# Fonte.net
KiCad netlist of a schematic drawn in Altium Designer
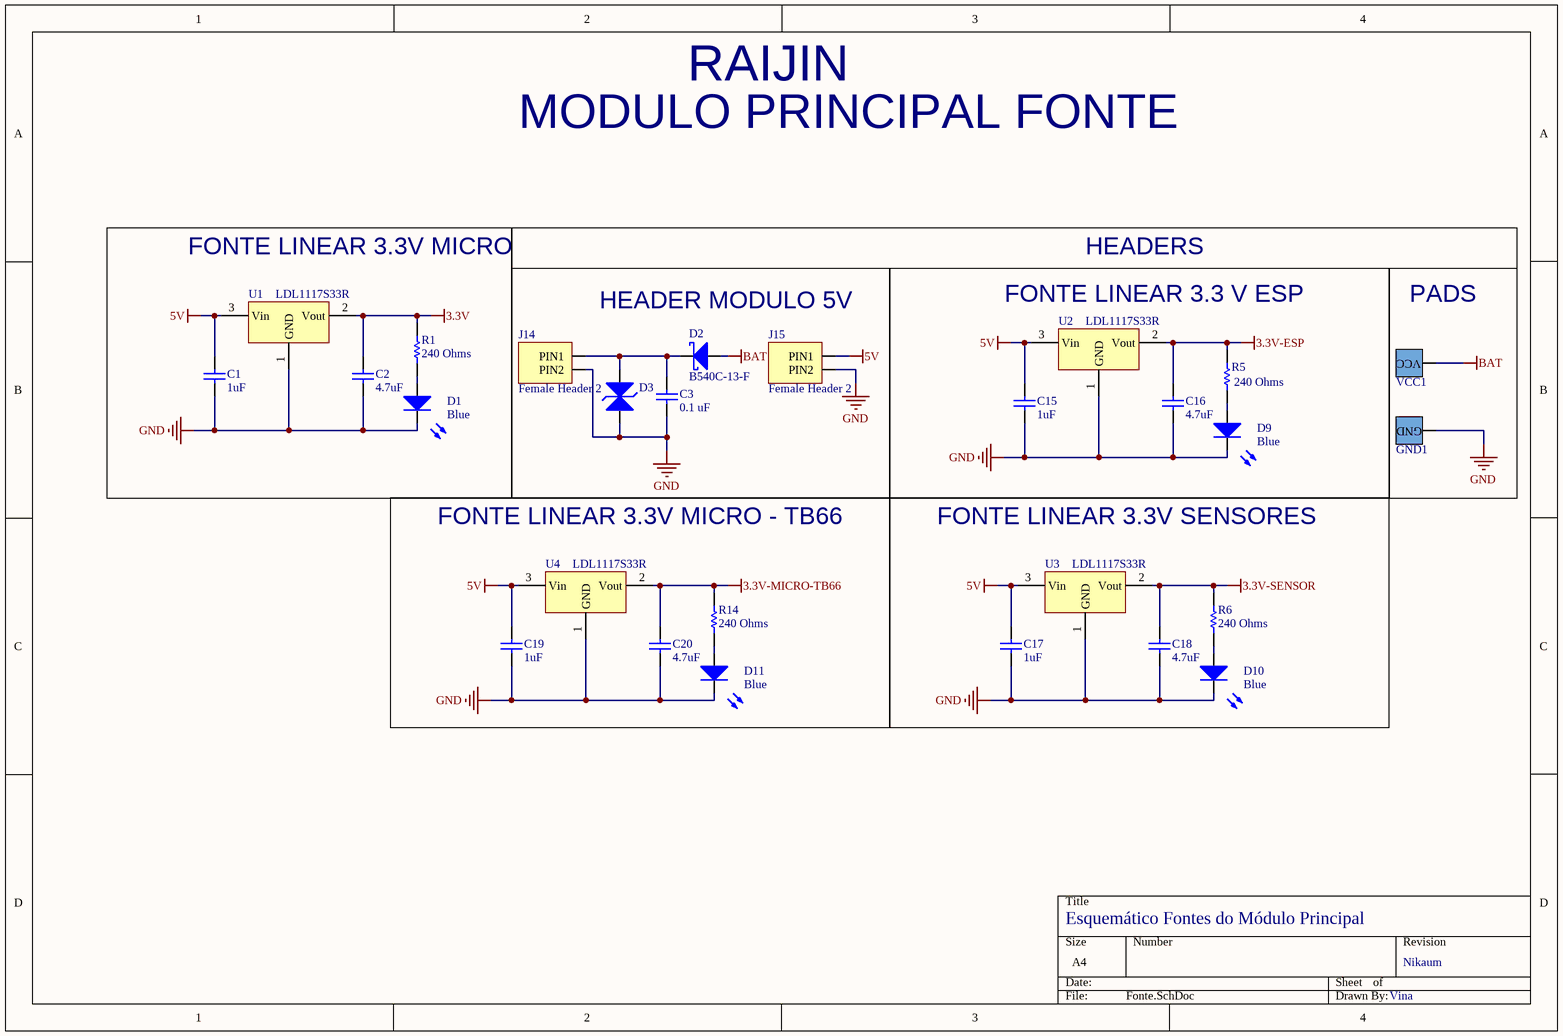
[diagram p0: Fonte.SchDoc]

(export (version "E")
  (design (tool "Eeschema 10.0.6"))
  (components
    (comp (ref "C1")
      (value "1uF")
      (footprint "C0805")
      (description "CAP CER 1uF 25V X5R 0805")
      (fields
        (field (name "MANUFACTURER") "Wurth Electronik")
        (field (name "PART NUMBER") "885012107015")
        (field (name "LIBRARY CONTROL - PERSON THAT CHECKED FOOTPRINT") "Nikaum")
        (field (name "LIBRARY CONTROL - PERSON THAT CHECKED SCHEMATIC") "Nikaum")
        (field (name "LIBRARY CONTROL - PERSON THAT DID THE LAST UPDATE FOOTPRINT") "Nikaum")
        (field (name "LIBRARY CONTROL - PERSON THAT DID THE LAST UPDATE SCHEMATIC") "Nikaum")
      )
      (libsource (lib "Uai!Tecas") (part "885012107015"))
    )
    (comp (ref "C2")
      (value "4.7uF")
      (footprint "C0805")
      (description "CAP CER 4.7uF 25V 20% 0805")
      (fields
        (field (name "MANUFACTURER") "Walsin")
        (field (name "PART NUMBER") "0805X475M250CT")
        (field (name "LIBRARY CONTROL - PERSON THAT CHECKED SCHEMATIC") "Guilherme")
        (field (name "LIBRARY CONTROL - PERSON THAT DID THE LAST UPDATE SCHEMATIC") "Marcos")
      )
      (libsource (lib "Uai!Tecas") (part "0805X475M250CT"))
    )
    (comp (ref "C3")
      (value "0.1 uF")
      (footprint "C0805")
      (description "CAP CER 0.1uF 50V X7R 0805")
      (fields
        (field (name "MANUFACTURER") "Kemet")
        (field (name "PART NUMBER") "C0805C104K5RACTU")
        (field (name "LIBRARY CONTROL - PERSON THAT CHECKED SCHEMATIC") "Guilherme")
        (field (name "LIBRARY CONTROL - PERSON THAT DID THE LAST UPDATE SCHEMATIC") "Marcos")
      )
      (libsource (lib "Uai!Tecas") (part "C0805C104K5RACTU"))
    )
    (comp (ref "C15")
      (value "1uF")
      (footprint "C0805")
      (description "CAP CER 1uF 25V X5R 0805")
      (fields
        (field (name "MANUFACTURER") "Wurth Electronik")
        (field (name "PART NUMBER") "885012107015")
        (field (name "LIBRARY CONTROL - PERSON THAT CHECKED FOOTPRINT") "Nikaum")
        (field (name "LIBRARY CONTROL - PERSON THAT CHECKED SCHEMATIC") "Nikaum")
        (field (name "LIBRARY CONTROL - PERSON THAT DID THE LAST UPDATE FOOTPRINT") "Nikaum")
        (field (name "LIBRARY CONTROL - PERSON THAT DID THE LAST UPDATE SCHEMATIC") "Nikaum")
      )
      (libsource (lib "Uai!Tecas") (part "885012107015"))
    )
    (comp (ref "C16")
      (value "4.7uF")
      (footprint "C0805")
      (description "CAP CER 4.7uF 25V 20% 0805")
      (fields
        (field (name "MANUFACTURER") "Walsin")
        (field (name "PART NUMBER") "0805X475M250CT")
        (field (name "LIBRARY CONTROL - PERSON THAT CHECKED SCHEMATIC") "Guilherme")
        (field (name "LIBRARY CONTROL - PERSON THAT DID THE LAST UPDATE SCHEMATIC") "Marcos")
      )
      (libsource (lib "Uai!Tecas") (part "0805X475M250CT"))
    )
    (comp (ref "C17")
      (value "1uF")
      (footprint "C0805")
      (description "CAP CER 1uF 25V X5R 0805")
      (fields
        (field (name "MANUFACTURER") "Wurth Electronik")
        (field (name "PART NUMBER") "885012107015")
        (field (name "LIBRARY CONTROL - PERSON THAT CHECKED FOOTPRINT") "Nikaum")
        (field (name "LIBRARY CONTROL - PERSON THAT CHECKED SCHEMATIC") "Nikaum")
        (field (name "LIBRARY CONTROL - PERSON THAT DID THE LAST UPDATE FOOTPRINT") "Nikaum")
        (field (name "LIBRARY CONTROL - PERSON THAT DID THE LAST UPDATE SCHEMATIC") "Nikaum")
      )
      (libsource (lib "Uai!Tecas") (part "885012107015"))
    )
    (comp (ref "C18")
      (value "4.7uF")
      (footprint "C0805")
      (description "CAP CER 4.7uF 25V 20% 0805")
      (fields
        (field (name "MANUFACTURER") "Walsin")
        (field (name "PART NUMBER") "0805X475M250CT")
        (field (name "LIBRARY CONTROL - PERSON THAT CHECKED SCHEMATIC") "Guilherme")
        (field (name "LIBRARY CONTROL - PERSON THAT DID THE LAST UPDATE SCHEMATIC") "Marcos")
      )
      (libsource (lib "Uai!Tecas") (part "0805X475M250CT"))
    )
    (comp (ref "C19")
      (value "1uF")
      (footprint "C0805")
      (description "CAP CER 1uF 25V X5R 0805")
      (fields
        (field (name "MANUFACTURER") "Wurth Electronik")
        (field (name "PART NUMBER") "885012107015")
        (field (name "LIBRARY CONTROL - PERSON THAT CHECKED FOOTPRINT") "Nikaum")
        (field (name "LIBRARY CONTROL - PERSON THAT CHECKED SCHEMATIC") "Nikaum")
        (field (name "LIBRARY CONTROL - PERSON THAT DID THE LAST UPDATE FOOTPRINT") "Nikaum")
        (field (name "LIBRARY CONTROL - PERSON THAT DID THE LAST UPDATE SCHEMATIC") "Nikaum")
      )
      (libsource (lib "Uai!Tecas") (part "885012107015"))
    )
    (comp (ref "C20")
      (value "4.7uF")
      (footprint "C0805")
      (description "CAP CER 4.7uF 25V 20% 0805")
      (fields
        (field (name "MANUFACTURER") "Walsin")
        (field (name "PART NUMBER") "0805X475M250CT")
        (field (name "LIBRARY CONTROL - PERSON THAT CHECKED SCHEMATIC") "Guilherme")
        (field (name "LIBRARY CONTROL - PERSON THAT DID THE LAST UPDATE SCHEMATIC") "Marcos")
      )
      (libsource (lib "Uai!Tecas") (part "0805X475M250CT"))
    )
    (comp (ref "D1")
      (value "Blue")
      (footprint "DIODO_2-SMD-3215")
      (description "LED 75mW BLUE 45MCD 3215")
      (fields
        (field (name "MANUFACTURER") "Everlight Electronics")
        (field (name "PART NUMBER") "EAST3215BA5")
        (field (name "LIBRARY CONTROL - PERSON THAT CHECKED FOOTPRINT") "Lucas")
        (field (name "LIBRARY CONTROL - PERSON THAT CHECKED SCHEMATIC") "Lucas")
        (field (name "LIBRARY CONTROL - PERSON THAT DID THE LAST UPDATE FOOTPRINT") "Stéfany (Ster)")
        (field (name "LIBRARY CONTROL - PERSON THAT DID THE LAST UPDATE SCHEMATIC") "Stéfany (Ster)")
      )
      (libsource (lib "Diodo") (part "EAST3215BA5"))
    )
    (comp (ref "D2")
      (value "B540C-13-F")
      (footprint "DIODO_DO-214AB")
      (description "DIODE SCHOTTKY 40V 5A DO-214AB")
      (fields
        (field (name "MANUFACTURER") "Diodes Incorporated")
        (field (name "LIBRARY CONTROL - PERSON THAT DID THE LAST UPDATE FOOTPRINT") "Dalarme")
        (field (name "LIBRARY CONTROL - PERSON THAT DID THE LAST UPDATE SCHEMATIC") "Stéfany(Ster)")
      )
      (libsource (lib "Uai!Tecas") (part "B540C-13-F"))
    )
    (comp (ref "D3")
      (value "ESD110B102ELE6327XTMA1")
      (footprint "DIODO-TSSLP-2-4")
      (description "DIODE TVS 26V 14.2A DO-214AA-2")
      (fields
        (field (name "MANUFACTURER") "Infineon")
        (field (name "LIBRARY CONTROL - PERSON THAT DID THE LAST UPDATE FOOTPRINT") "Nikaum")
        (field (name "LIBRARY CONTROL - PERSON THAT DID THE LAST UPDATE SCHEMATIC") "Nikaum")
      )
      (libsource (lib "Uai!Tecas") (part "ESD110B102ELE6327XTMA1"))
    )
    (comp (ref "D9")
      (value "Blue")
      (footprint "DIODO_2-SMD-3215")
      (description "LED 75mW BLUE 45MCD 3215")
      (fields
        (field (name "MANUFACTURER") "Everlight Electronics")
        (field (name "PART NUMBER") "EAST3215BA5")
        (field (name "LIBRARY CONTROL - PERSON THAT CHECKED FOOTPRINT") "Lucas")
        (field (name "LIBRARY CONTROL - PERSON THAT CHECKED SCHEMATIC") "Lucas")
        (field (name "LIBRARY CONTROL - PERSON THAT DID THE LAST UPDATE FOOTPRINT") "Stéfany (Ster)")
        (field (name "LIBRARY CONTROL - PERSON THAT DID THE LAST UPDATE SCHEMATIC") "Stéfany (Ster)")
      )
      (libsource (lib "Diodo") (part "EAST3215BA5"))
    )
    (comp (ref "D10")
      (value "Blue")
      (footprint "DIODO_2-SMD-3215")
      (description "LED 75mW BLUE 45MCD 3215")
      (fields
        (field (name "MANUFACTURER") "Everlight Electronics")
        (field (name "PART NUMBER") "EAST3215BA5")
        (field (name "LIBRARY CONTROL - PERSON THAT CHECKED FOOTPRINT") "Lucas")
        (field (name "LIBRARY CONTROL - PERSON THAT CHECKED SCHEMATIC") "Lucas")
        (field (name "LIBRARY CONTROL - PERSON THAT DID THE LAST UPDATE FOOTPRINT") "Stéfany (Ster)")
        (field (name "LIBRARY CONTROL - PERSON THAT DID THE LAST UPDATE SCHEMATIC") "Stéfany (Ster)")
      )
      (libsource (lib "Diodo") (part "EAST3215BA5"))
    )
    (comp (ref "D11")
      (value "Blue")
      (footprint "DIODO_2-SMD-3215")
      (description "LED 75mW BLUE 45MCD 3215")
      (fields
        (field (name "MANUFACTURER") "Everlight Electronics")
        (field (name "PART NUMBER") "EAST3215BA5")
        (field (name "LIBRARY CONTROL - PERSON THAT CHECKED FOOTPRINT") "Lucas")
        (field (name "LIBRARY CONTROL - PERSON THAT CHECKED SCHEMATIC") "Lucas")
        (field (name "LIBRARY CONTROL - PERSON THAT DID THE LAST UPDATE FOOTPRINT") "Stéfany (Ster)")
        (field (name "LIBRARY CONTROL - PERSON THAT DID THE LAST UPDATE SCHEMATIC") "Stéfany (Ster)")
      )
      (libsource (lib "Diodo") (part "EAST3215BA5"))
    )
    (comp (ref "GND1")
      (value "Ground Pad")
      (footprint "PAD_ALIMENTAÇÃO_MINI")
      (description "GND PAD MINI SUMÔ")
      (libsource (lib "Uai!Tecas") (part "Ground Pad Mini Sumô"))
    )
    (comp (ref "J14")
      (value "Female Header 2")
      (footprint "Female Header 2")
      (libsource (lib "Uai!Tecas") (part "Female Header 2"))
    )
    (comp (ref "J15")
      (value "Female Header 2")
      (footprint "Female Header 2")
      (libsource (lib "Uai!Tecas") (part "Female Header 2"))
    )
    (comp (ref "R1")
      (value "240 Ohms")
      (footprint "RESC1608X55N")
      (description "RES SMD 240 OHM 1% 1/10W 0603")
      (fields (field (name "MANUFACTURER") "YAGEO") (field (name "PART NUMBER") "RC0603FR-07240RL"))
      (libsource (lib "Uai!Tecas") (part "RC0603FR-07240RL"))
    )
    (comp (ref "R5")
      (value "240 Ohms")
      (footprint "RESC1608X55N")
      (description "RES SMD 240 OHM 1% 1/10W 0603")
      (fields (field (name "MANUFACTURER") "YAGEO") (field (name "PART NUMBER") "RC0603FR-07240RL"))
      (libsource (lib "Uai!Tecas") (part "RC0603FR-07240RL"))
    )
    (comp (ref "R6")
      (value "240 Ohms")
      (footprint "RESC1608X55N")
      (description "RES SMD 240 OHM 1% 1/10W 0603")
      (fields (field (name "MANUFACTURER") "YAGEO") (field (name "PART NUMBER") "RC0603FR-07240RL"))
      (libsource (lib "Uai!Tecas") (part "RC0603FR-07240RL"))
    )
    (comp (ref "R14")
      (value "240 Ohms")
      (footprint "RESC1608X55N")
      (description "RES SMD 240 OHM 1% 1/10W 0603")
      (fields (field (name "MANUFACTURER") "YAGEO") (field (name "PART NUMBER") "RC0603FR-07240RL"))
      (libsource (lib "Uai!Tecas") (part "RC0603FR-07240RL"))
    )
    (comp (ref "U1")
      (value "LDL1117S33R")
      (footprint "SOT-223-4")
      (description "IC REG LINEAR 3.3V 1.2A SOT-223-4")
      (fields
        (field (name "MANUFACTURER") "STMicroelectronics")
        (field (name "LIBRARY CONTROL - PERSON THAT CHECKED FOOTPRINT") "Nícolas")
        (field (name "LIBRARY CONTROL - PERSON THAT CHECKED SCHEMATIC") "Nícolas")
        (field (name "LIBRARY CONTROL - PERSON THAT DID THE LAST UPDATE FOOTPRINT") "Pierre")
        (field (name "LIBRARY CONTROL - PERSON THAT DID THE LAST UPDATE SCHEMATIC") "Nícolas")
      )
      (libsource (lib "Uai!Tecas") (part "LDL1117S33R"))
    )
    (comp (ref "U2")
      (value "LDL1117S33R")
      (footprint "SOT-223-4")
      (description "IC REG LINEAR 3.3V 1.2A SOT-223-4")
      (fields
        (field (name "MANUFACTURER") "STMicroelectronics")
        (field (name "LIBRARY CONTROL - PERSON THAT CHECKED FOOTPRINT") "Nícolas")
        (field (name "LIBRARY CONTROL - PERSON THAT CHECKED SCHEMATIC") "Nícolas")
        (field (name "LIBRARY CONTROL - PERSON THAT DID THE LAST UPDATE FOOTPRINT") "Pierre")
        (field (name "LIBRARY CONTROL - PERSON THAT DID THE LAST UPDATE SCHEMATIC") "Nícolas")
      )
      (libsource (lib "Uai!Tecas") (part "LDL1117S33R"))
    )
    (comp (ref "U3")
      (value "LDL1117S33R")
      (footprint "SOT-223-4")
      (description "IC REG LINEAR 3.3V 1.2A SOT-223-4")
      (fields
        (field (name "MANUFACTURER") "STMicroelectronics")
        (field (name "LIBRARY CONTROL - PERSON THAT CHECKED FOOTPRINT") "Nícolas")
        (field (name "LIBRARY CONTROL - PERSON THAT CHECKED SCHEMATIC") "Nícolas")
        (field (name "LIBRARY CONTROL - PERSON THAT DID THE LAST UPDATE FOOTPRINT") "Pierre")
        (field (name "LIBRARY CONTROL - PERSON THAT DID THE LAST UPDATE SCHEMATIC") "Nícolas")
      )
      (libsource (lib "Uai!Tecas") (part "LDL1117S33R"))
    )
    (comp (ref "U4")
      (value "LDL1117S33R")
      (footprint "SOT-223-4")
      (description "IC REG LINEAR 3.3V 1.2A SOT-223-4")
      (fields
        (field (name "MANUFACTURER") "STMicroelectronics")
        (field (name "LIBRARY CONTROL - PERSON THAT CHECKED FOOTPRINT") "Nícolas")
        (field (name "LIBRARY CONTROL - PERSON THAT CHECKED SCHEMATIC") "Nícolas")
        (field (name "LIBRARY CONTROL - PERSON THAT DID THE LAST UPDATE FOOTPRINT") "Pierre")
        (field (name "LIBRARY CONTROL - PERSON THAT DID THE LAST UPDATE SCHEMATIC") "Nícolas")
      )
      (libsource (lib "Uai!Tecas") (part "LDL1117S33R"))
    )
    (comp (ref "VCC1")
      (value "Source Pad")
      (footprint "PAD_ALIMENTAÇÃO_MINI")
      (description "VCC PAD MINI SUMÔ")
      (libsource (lib "Uai!Tecas") (part "Source Pad Mini Sumô"))
    )
  )
  (nets
    (net (code "1") (name "3.3V") (class "Default")
      (node (ref "C2") (pin "2") (pinfunction "2_2") (pintype "passive"))
      (node (ref "R1") (pin "2") (pinfunction "2_2") (pintype "passive"))
      (node (ref "U1") (pin "2") (pinfunction "Vout_2") (pintype "power_in"))
    )
    (net (code "2") (name "3.3V-ESP") (class "Default")
      (node (ref "C16") (pin "2") (pinfunction "2_2") (pintype "passive"))
      (node (ref "R5") (pin "2") (pinfunction "2_2") (pintype "passive"))
      (node (ref "U2") (pin "2") (pinfunction "Vout_2") (pintype "power_in"))
    )
    (net (code "3") (name "3.3V-MICRO-TB66") (class "Default")
      (node (ref "C20") (pin "2") (pinfunction "2_2") (pintype "passive"))
      (node (ref "R14") (pin "2") (pinfunction "2_2") (pintype "passive"))
      (node (ref "U4") (pin "2") (pinfunction "Vout_2") (pintype "power_in"))
    )
    (net (code "4") (name "3.3V-SENSOR") (class "Default")
      (node (ref "C18") (pin "2") (pinfunction "2_2") (pintype "passive"))
      (node (ref "R6") (pin "2") (pinfunction "2_2") (pintype "passive"))
      (node (ref "U3") (pin "2") (pinfunction "Vout_2") (pintype "power_in"))
    )
    (net (code "5") (name "5V") (class "Default")
      (node (ref "C1") (pin "2") (pinfunction "2_2") (pintype "passive"))
      (node (ref "C15") (pin "2") (pinfunction "2_2") (pintype "passive"))
      (node (ref "C17") (pin "2") (pinfunction "2_2") (pintype "passive"))
      (node (ref "C19") (pin "2") (pinfunction "2_2") (pintype "passive"))
      (node (ref "J15") (pin "PIN1") (pinfunction "PIN1_PIN1") (pintype "passive"))
      (node (ref "U1") (pin "3") (pinfunction "Vin_3") (pintype "power_in"))
      (node (ref "U2") (pin "3") (pinfunction "Vin_3") (pintype "power_in"))
      (node (ref "U3") (pin "3") (pinfunction "Vin_3") (pintype "power_in"))
      (node (ref "U4") (pin "3") (pinfunction "Vin_3") (pintype "power_in"))
    )
    (net (code "6") (name "BAT") (class "Default")
      (node (ref "D2") (pin "A") (pinfunction "A_A") (pintype "passive"))
      (node (ref "VCC1") (pin "A") (pinfunction "VCC_A") (pintype "passive"))
    )
    (net (code "7") (name "GND") (class "Default")
      (node (ref "C1") (pin "1") (pinfunction "1_1") (pintype "passive"))
      (node (ref "C15") (pin "1") (pinfunction "1_1") (pintype "passive"))
      (node (ref "C16") (pin "1") (pinfunction "1_1") (pintype "passive"))
      (node (ref "C17") (pin "1") (pinfunction "1_1") (pintype "passive"))
      (node (ref "C18") (pin "1") (pinfunction "1_1") (pintype "passive"))
      (node (ref "C19") (pin "1") (pinfunction "1_1") (pintype "passive"))
      (node (ref "C2") (pin "1") (pinfunction "1_1") (pintype "passive"))
      (node (ref "C20") (pin "1") (pinfunction "1_1") (pintype "passive"))
      (node (ref "C3") (pin "2") (pinfunction "2_2") (pintype "passive"))
      (node (ref "D1") (pin "C") (pinfunction "C_C") (pintype "passive"))
      (node (ref "D10") (pin "C") (pinfunction "C_C") (pintype "passive"))
      (node (ref "D11") (pin "C") (pinfunction "C_C") (pintype "passive"))
      (node (ref "D3") (pin "A") (pinfunction "A_A") (pintype "passive"))
      (node (ref "D9") (pin "C") (pinfunction "C_C") (pintype "passive"))
      (node (ref "GND1") (pin "A") (pinfunction "GND_A") (pintype "passive"))
      (node (ref "J14") (pin "PIN2") (pinfunction "PIN2_PIN2") (pintype "passive"))
      (node (ref "J15") (pin "PIN2") (pinfunction "PIN2_PIN2") (pintype "passive"))
      (node (ref "U1") (pin "1") (pinfunction "GND_1") (pintype "power_in"))
      (node (ref "U2") (pin "1") (pinfunction "GND_1") (pintype "power_in"))
      (node (ref "U3") (pin "1") (pinfunction "GND_1") (pintype "power_in"))
      (node (ref "U4") (pin "1") (pinfunction "GND_1") (pintype "power_in"))
    )
    (net (code "8") (name "Net-(C3-Pad1)") (class "Default")
      (node (ref "C3") (pin "1") (pinfunction "1_1") (pintype "passive"))
      (node (ref "D2") (pin "C") (pinfunction "C_C") (pintype "passive"))
      (node (ref "D3") (pin "C") (pinfunction "C_C") (pintype "passive"))
      (node (ref "J14") (pin "PIN1") (pinfunction "PIN1_PIN1") (pintype "passive"))
    )
    (net (code "9") (name "Net-(D1-PadA)") (class "Default")
      (node (ref "D1") (pin "A") (pinfunction "A_A") (pintype "passive"))
      (node (ref "R1") (pin "1") (pinfunction "1_1") (pintype "passive"))
    )
    (net (code "10") (name "Net-(D9-PadA)") (class "Default")
      (node (ref "D9") (pin "A") (pinfunction "A_A") (pintype "passive"))
      (node (ref "R5") (pin "1") (pinfunction "1_1") (pintype "passive"))
    )
    (net (code "11") (name "Net-(D10-PadA)") (class "Default")
      (node (ref "D10") (pin "A") (pinfunction "A_A") (pintype "passive"))
      (node (ref "R6") (pin "1") (pinfunction "1_1") (pintype "passive"))
    )
    (net (code "12") (name "Net-(D11-PadA)") (class "Default")
      (node (ref "D11") (pin "A") (pinfunction "A_A") (pintype "passive"))
      (node (ref "R14") (pin "1") (pinfunction "1_1") (pintype "passive"))
    )
  )
)
